# Borne.net
KiCad netlist of a schematic drawn in Altium Designer
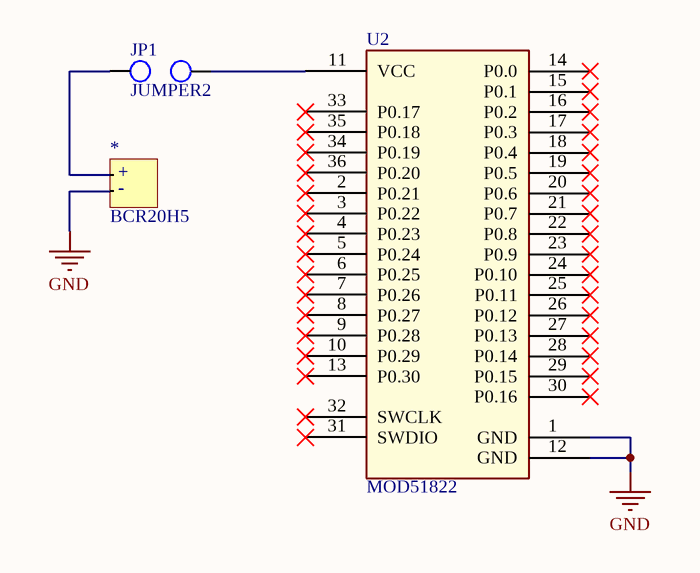
[diagram p0: Borne.SchDoc]

(export (version "E")
  (design (tool "Eeschema 10.0.6"))
  (components
    (comp (ref "*") (value "BCR20H5") (footprint "BCR20H5") (libsource (lib "MyComponent") (part "BCR20H5")))
    (comp (ref "JP1")
      (value "JUMPER2")
      (footprint "BARRETTE_2_M_D")
      (description "BARRETTE 2 CONTACTS 1 RANGEE MALE DROITE")
      (fields (field (name "TYPE") "JUMPER2"))
      (libsource (lib "connecteurs") (part "JUMPER2"))
    )
    (comp (ref "U2")
      (value "MOD51822")
      (footprint "MOD51822")
      (libsource (lib "Projets_OC") (part "MOD51822"))
    )
  )
  (nets
    (net (code "1") (name "GND") (class "Default")
      (node (ref "*") (pin "2") (pinfunction "2_2") (pintype "passive"))
      (node (ref "U2") (pin "1") (pinfunction "GND_1") (pintype "passive"))
      (node (ref "U2") (pin "12") (pinfunction "GND_12") (pintype "passive"))
    )
    (net (code "2") (name "Net-(*-Pad1)") (class "Default")
      (node (ref "*") (pin "1") (pinfunction "1_1") (pintype "passive"))
      (node (ref "JP1") (pin "1") (pinfunction "1_1") (pintype "passive"))
    )
    (net (code "3") (name "Net-(U2-VCC)") (class "Default")
      (node (ref "JP1") (pin "2") (pinfunction "2_2") (pintype "passive"))
      (node (ref "U2") (pin "11") (pinfunction "VCC_11") (pintype "passive"))
    )
    (net (code "4") (name "unconnected-(U2-P0.0-Pad14)") (class "Default")
      (node (ref "U2") (pin "14") (pinfunction "P0.0_14") (pintype "passive+no_connect"))
    )
    (net (code "5") (name "unconnected-(U2-P0.1-Pad15)") (class "Default")
      (node (ref "U2") (pin "15") (pinfunction "P0.1_15") (pintype "passive+no_connect"))
    )
    (net (code "6") (name "unconnected-(U2-P0.2-Pad16)") (class "Default")
      (node (ref "U2") (pin "16") (pinfunction "P0.2_16") (pintype "passive+no_connect"))
    )
    (net (code "7") (name "unconnected-(U2-P0.3-Pad17)") (class "Default")
      (node (ref "U2") (pin "17") (pinfunction "P0.3_17") (pintype "passive+no_connect"))
    )
    (net (code "8") (name "unconnected-(U2-P0.4-Pad18)") (class "Default")
      (node (ref "U2") (pin "18") (pinfunction "P0.4_18") (pintype "passive+no_connect"))
    )
    (net (code "9") (name "unconnected-(U2-P0.5-Pad19)") (class "Default")
      (node (ref "U2") (pin "19") (pinfunction "P0.5_19") (pintype "passive+no_connect"))
    )
    (net (code "10") (name "unconnected-(U2-P0.6-Pad20)") (class "Default")
      (node (ref "U2") (pin "20") (pinfunction "P0.6_20") (pintype "passive+no_connect"))
    )
    (net (code "11") (name "unconnected-(U2-P0.7-Pad21)") (class "Default")
      (node (ref "U2") (pin "21") (pinfunction "P0.7_21") (pintype "passive+no_connect"))
    )
    (net (code "12") (name "unconnected-(U2-P0.8-Pad22)") (class "Default")
      (node (ref "U2") (pin "22") (pinfunction "P0.8_22") (pintype "passive+no_connect"))
    )
    (net (code "13") (name "unconnected-(U2-P0.9-Pad23)") (class "Default")
      (node (ref "U2") (pin "23") (pinfunction "P0.9_23") (pintype "passive+no_connect"))
    )
    (net (code "14") (name "unconnected-(U2-P0.10-Pad24)") (class "Default")
      (node (ref "U2") (pin "24") (pinfunction "P0.10_24") (pintype "passive+no_connect"))
    )
    (net (code "15") (name "unconnected-(U2-P0.11-Pad25)") (class "Default")
      (node (ref "U2") (pin "25") (pinfunction "P0.11_25") (pintype "passive+no_connect"))
    )
    (net (code "16") (name "unconnected-(U2-P0.12-Pad26)") (class "Default")
      (node (ref "U2") (pin "26") (pinfunction "P0.12_26") (pintype "passive+no_connect"))
    )
    (net (code "17") (name "unconnected-(U2-P0.13-Pad27)") (class "Default")
      (node (ref "U2") (pin "27") (pinfunction "P0.13_27") (pintype "passive+no_connect"))
    )
    (net (code "18") (name "unconnected-(U2-P0.14-Pad28)") (class "Default")
      (node (ref "U2") (pin "28") (pinfunction "P0.14_28") (pintype "passive+no_connect"))
    )
    (net (code "19") (name "unconnected-(U2-P0.15-Pad29)") (class "Default")
      (node (ref "U2") (pin "29") (pinfunction "P0.15_29") (pintype "passive+no_connect"))
    )
    (net (code "20") (name "unconnected-(U2-P0.16-Pad30)") (class "Default")
      (node (ref "U2") (pin "30") (pinfunction "P0.16_30") (pintype "passive+no_connect"))
    )
    (net (code "21") (name "unconnected-(U2-P0.17-Pad33)") (class "Default")
      (node (ref "U2") (pin "33") (pinfunction "P0.17_33") (pintype "passive+no_connect"))
    )
    (net (code "22") (name "unconnected-(U2-P0.18-Pad35)") (class "Default")
      (node (ref "U2") (pin "35") (pinfunction "P0.18_35") (pintype "passive+no_connect"))
    )
    (net (code "23") (name "unconnected-(U2-P0.19-Pad34)") (class "Default")
      (node (ref "U2") (pin "34") (pinfunction "P0.19_34") (pintype "passive+no_connect"))
    )
    (net (code "24") (name "unconnected-(U2-P0.20-Pad36)") (class "Default")
      (node (ref "U2") (pin "36") (pinfunction "P0.20_36") (pintype "passive+no_connect"))
    )
    (net (code "25") (name "unconnected-(U2-P0.21-Pad2)") (class "Default")
      (node (ref "U2") (pin "2") (pinfunction "P0.21_2") (pintype "passive+no_connect"))
    )
    (net (code "26") (name "unconnected-(U2-P0.22-Pad3)") (class "Default")
      (node (ref "U2") (pin "3") (pinfunction "P0.22_3") (pintype "passive+no_connect"))
    )
    (net (code "27") (name "unconnected-(U2-P0.23-Pad4)") (class "Default")
      (node (ref "U2") (pin "4") (pinfunction "P0.23_4") (pintype "passive+no_connect"))
    )
    (net (code "28") (name "unconnected-(U2-P0.24-Pad5)") (class "Default")
      (node (ref "U2") (pin "5") (pinfunction "P0.24_5") (pintype "passive+no_connect"))
    )
    (net (code "29") (name "unconnected-(U2-P0.25-Pad6)") (class "Default")
      (node (ref "U2") (pin "6") (pinfunction "P0.25_6") (pintype "passive+no_connect"))
    )
    (net (code "30") (name "unconnected-(U2-P0.26-Pad7)") (class "Default")
      (node (ref "U2") (pin "7") (pinfunction "P0.26_7") (pintype "passive+no_connect"))
    )
    (net (code "31") (name "unconnected-(U2-P0.27-Pad8)") (class "Default")
      (node (ref "U2") (pin "8") (pinfunction "P0.27_8") (pintype "passive+no_connect"))
    )
    (net (code "32") (name "unconnected-(U2-P0.28-Pad9)") (class "Default")
      (node (ref "U2") (pin "9") (pinfunction "P0.28_9") (pintype "passive+no_connect"))
    )
    (net (code "33") (name "unconnected-(U2-P0.29-Pad10)") (class "Default")
      (node (ref "U2") (pin "10") (pinfunction "P0.29_10") (pintype "passive+no_connect"))
    )
    (net (code "34") (name "unconnected-(U2-P0.30-Pad13)") (class "Default")
      (node (ref "U2") (pin "13") (pinfunction "P0.30_13") (pintype "passive+no_connect"))
    )
    (net (code "35") (name "unconnected-(U2-SWCLK-Pad32)") (class "Default")
      (node (ref "U2") (pin "32") (pinfunction "SWCLK_32") (pintype "passive+no_connect"))
    )
    (net (code "36") (name "unconnected-(U2-SWDIO-Pad31)") (class "Default")
      (node (ref "U2") (pin "31") (pinfunction "SWDIO_31") (pintype "passive+no_connect"))
    )
  )
)
